# Op_Amp_Sig_Process.net
KiCad netlist of a schematic drawn in Altium Designer
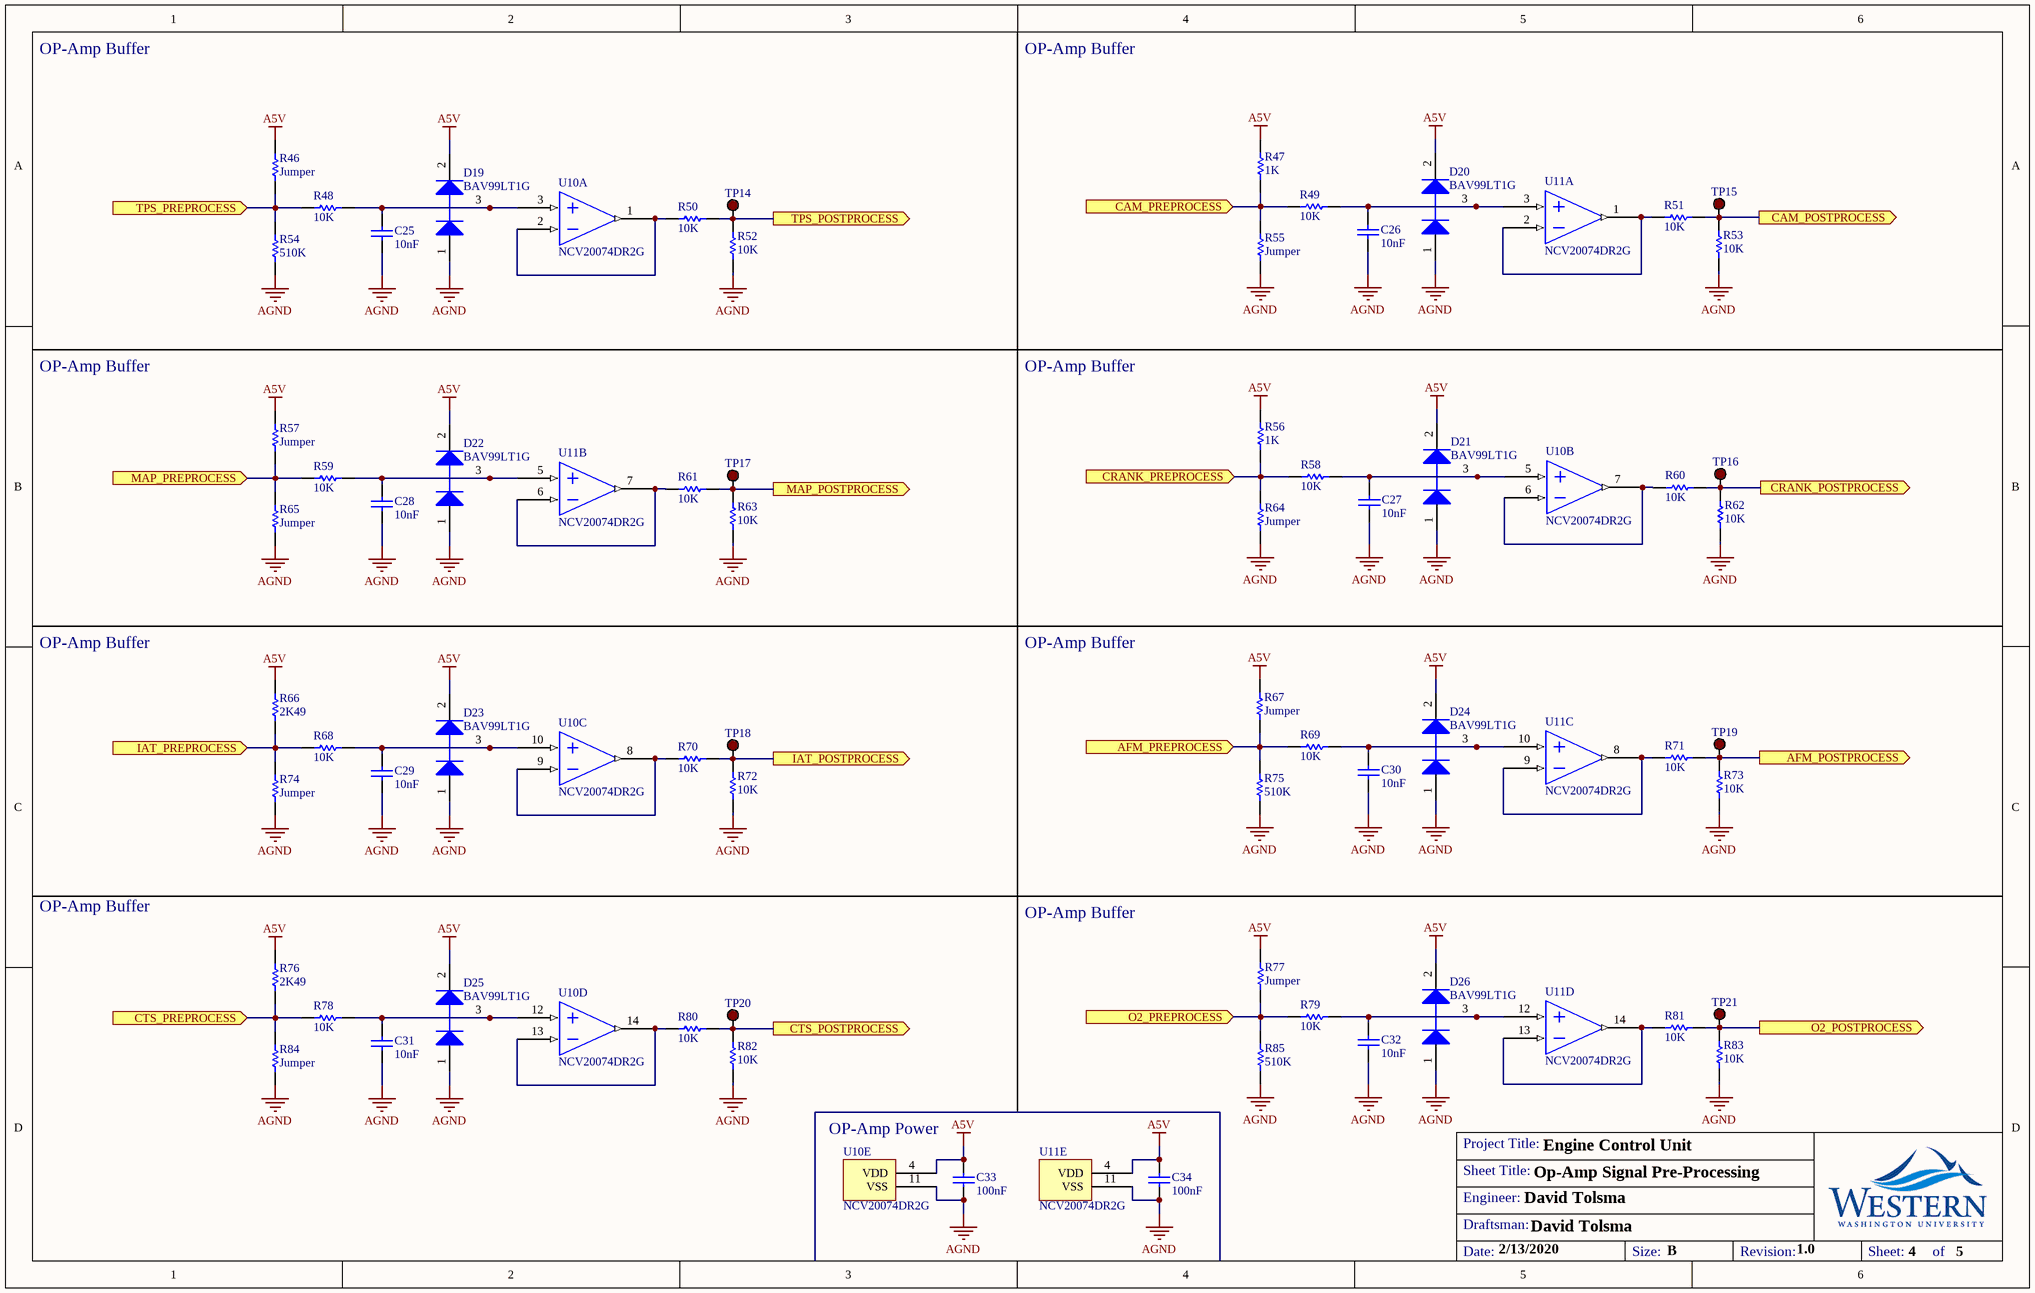
[diagram p0: Op_Amp_Sig_Process.SchDoc]

(export (version "E")
  (design (tool "Eeschema 10.0.6"))
  (components
    (comp (ref "C25")
      (value "10nF")
      (footprint "CAPC0603(1608)100_M")
      (description "CAP 10nF 50V ±5% 0603 (1608 Metric) Thickness 1mm SMD")
      (fields (field (name "TOLERANCE") "Â±5%"))
      (libsource (lib "Altium Content Vault") (part "CAP"))
    )
    (comp (ref "C26")
      (value "10nF")
      (footprint "CAPC0603(1608)100_M")
      (description "CAP 10nF 50V ±5% 0603 (1608 Metric) Thickness 1mm SMD")
      (fields (field (name "TOLERANCE") "Â±5%"))
      (libsource (lib "Altium Content Vault") (part "CAP"))
    )
    (comp (ref "C27")
      (value "10nF")
      (footprint "CAPC0603(1608)100_M")
      (description "CAP 10nF 50V ±5% 0603 (1608 Metric) Thickness 1mm SMD")
      (fields (field (name "TOLERANCE") "Â±5%"))
      (libsource (lib "Altium Content Vault") (part "CAP"))
    )
    (comp (ref "C28")
      (value "10nF")
      (footprint "CAPC0603(1608)100_M")
      (description "CAP 10nF 50V ±5% 0603 (1608 Metric) Thickness 1mm SMD")
      (fields (field (name "TOLERANCE") "Â±5%"))
      (libsource (lib "Altium Content Vault") (part "CAP"))
    )
    (comp (ref "C29")
      (value "10nF")
      (footprint "CAPC0603(1608)100_M")
      (description "CAP 10nF 50V ±5% 0603 (1608 Metric) Thickness 1mm SMD")
      (fields (field (name "TOLERANCE") "Â±5%"))
      (libsource (lib "Altium Content Vault") (part "CAP"))
    )
    (comp (ref "C30")
      (value "10nF")
      (footprint "CAPC0603(1608)100_M")
      (description "CAP 10nF 50V ±5% 0603 (1608 Metric) Thickness 1mm SMD")
      (fields (field (name "TOLERANCE") "Â±5%"))
      (libsource (lib "Altium Content Vault") (part "CAP"))
    )
    (comp (ref "C31")
      (value "10nF")
      (footprint "CAPC0603(1608)100_M")
      (description "CAP 10nF 50V ±5% 0603 (1608 Metric) Thickness 1mm SMD")
      (fields (field (name "TOLERANCE") "Â±5%"))
      (libsource (lib "Altium Content Vault") (part "CAP"))
    )
    (comp (ref "C32")
      (value "10nF")
      (footprint "CAPC0603(1608)100_M")
      (description "CAP 10nF 50V ±5% 0603 (1608 Metric) Thickness 1mm SMD")
      (fields (field (name "TOLERANCE") "Â±5%"))
      (libsource (lib "Altium Content Vault") (part "CAP"))
    )
    (comp (ref "C33")
      (value "100nF")
      (footprint "CAPC0603(1608)100_M")
      (description "CAP 100nF 10V ±10% 0603 (1608 Metric) Thickness 1mm SMD")
      (fields (field (name "TOLERANCE") "Â±10%"))
      (libsource (lib "Altium Content Vault") (part "CAP"))
    )
    (comp (ref "C34")
      (value "100nF")
      (footprint "CAPC0603(1608)100_M")
      (description "CAP 100nF 10V ±10% 0603 (1608 Metric) Thickness 1mm SMD")
      (fields (field (name "TOLERANCE") "Â±10%"))
      (libsource (lib "Altium Content Vault") (part "CAP"))
    )
    (comp (ref "D19")
      (value "BAV99LT1G")
      (footprint "ONSC-SOT-23-3-318-08_V")
      (description "Dual Series Switching Diodes, 3-Pin SOT-23, Pb-Free, Tape and Reel")
      (fields (field (name "MANUFACTURER") "On Semiconductor"))
      (libsource (lib "Altium Content Vault") (part "ONSC-D-A1K2C3-3"))
    )
    (comp (ref "D20")
      (value "BAV99LT1G")
      (footprint "ONSC-SOT-23-3-318-08_V")
      (description "Dual Series Switching Diodes, 3-Pin SOT-23, Pb-Free, Tape and Reel")
      (fields (field (name "MANUFACTURER") "On Semiconductor"))
      (libsource (lib "Altium Content Vault") (part "ONSC-D-A1K2C3-3"))
    )
    (comp (ref "D21")
      (value "BAV99LT1G")
      (footprint "ONSC-SOT-23-3-318-08_V")
      (description "Dual Series Switching Diodes, 3-Pin SOT-23, Pb-Free, Tape and Reel")
      (fields (field (name "MANUFACTURER") "On Semiconductor"))
      (libsource (lib "Altium Content Vault") (part "ONSC-D-A1K2C3-3"))
    )
    (comp (ref "D22")
      (value "BAV99LT1G")
      (footprint "ONSC-SOT-23-3-318-08_V")
      (description "Dual Series Switching Diodes, 3-Pin SOT-23, Pb-Free, Tape and Reel")
      (fields (field (name "MANUFACTURER") "On Semiconductor"))
      (libsource (lib "Altium Content Vault") (part "ONSC-D-A1K2C3-3"))
    )
    (comp (ref "D23")
      (value "BAV99LT1G")
      (footprint "ONSC-SOT-23-3-318-08_V")
      (description "Dual Series Switching Diodes, 3-Pin SOT-23, Pb-Free, Tape and Reel")
      (fields (field (name "MANUFACTURER") "On Semiconductor"))
      (libsource (lib "Altium Content Vault") (part "ONSC-D-A1K2C3-3"))
    )
    (comp (ref "D24")
      (value "BAV99LT1G")
      (footprint "ONSC-SOT-23-3-318-08_V")
      (description "Dual Series Switching Diodes, 3-Pin SOT-23, Pb-Free, Tape and Reel")
      (fields (field (name "MANUFACTURER") "On Semiconductor"))
      (libsource (lib "Altium Content Vault") (part "ONSC-D-A1K2C3-3"))
    )
    (comp (ref "D25")
      (value "BAV99LT1G")
      (footprint "ONSC-SOT-23-3-318-08_V")
      (description "Dual Series Switching Diodes, 3-Pin SOT-23, Pb-Free, Tape and Reel")
      (fields (field (name "MANUFACTURER") "On Semiconductor"))
      (libsource (lib "Altium Content Vault") (part "ONSC-D-A1K2C3-3"))
    )
    (comp (ref "D26")
      (value "BAV99LT1G")
      (footprint "ONSC-SOT-23-3-318-08_V")
      (description "Dual Series Switching Diodes, 3-Pin SOT-23, Pb-Free, Tape and Reel")
      (fields (field (name "MANUFACTURER") "On Semiconductor"))
      (libsource (lib "Altium Content Vault") (part "ONSC-D-A1K2C3-3"))
    )
    (comp (ref "R46")
      (value "Jumper")
      (footprint "RESC0603(1608)_M")
      (description "Jumper 0603 (1608 Metric)")
      (fields (field (name "POWER") "None"))
      (libsource (lib "Altium Content Vault") (part "RES"))
    )
    (comp (ref "R47")
      (value "1K")
      (footprint "RESC0603(1608)_M")
      (description "1K 0.1W 1% 0603 (1608 Metric)  SMD")
      (fields (field (name "TOLERANCE") "1 %") (field (name "POWER") "0.1 W"))
      (libsource (lib "Altium Content Vault") (part "RES"))
    )
    (comp (ref "R48")
      (value "10K")
      (footprint "RESC0603(1608)_M")
      (description "10K 0.1W 1% 0603 (1608 Metric)  SMD")
      (fields (field (name "POWER") "0.1 W") (field (name "TOLERANCE") "1 %"))
      (libsource (lib "Altium Content Vault") (part "RES"))
    )
    (comp (ref "R49")
      (value "10K")
      (footprint "RESC0603(1608)_M")
      (description "10K 0.1W 1% 0603 (1608 Metric)  SMD")
      (fields (field (name "POWER") "0.1 W") (field (name "TOLERANCE") "1 %"))
      (libsource (lib "Altium Content Vault") (part "RES"))
    )
    (comp (ref "R50")
      (value "10K")
      (footprint "RESC0603(1608)_M")
      (description "10K 0.1W 1% 0603 (1608 Metric)  SMD")
      (fields (field (name "POWER") "0.1 W") (field (name "TOLERANCE") "1 %"))
      (libsource (lib "Altium Content Vault") (part "RES"))
    )
    (comp (ref "R51")
      (value "10K")
      (footprint "RESC0603(1608)_M")
      (description "10K 0.1W 1% 0603 (1608 Metric)  SMD")
      (fields (field (name "POWER") "0.1 W") (field (name "TOLERANCE") "1 %"))
      (libsource (lib "Altium Content Vault") (part "RES"))
    )
    (comp (ref "R52")
      (value "10K")
      (footprint "RESC0603(1608)_M")
      (description "10K 0.1W 1% 0603 (1608 Metric)  SMD")
      (fields (field (name "POWER") "0.1 W") (field (name "TOLERANCE") "1 %"))
      (libsource (lib "Altium Content Vault") (part "RES"))
    )
    (comp (ref "R53")
      (value "10K")
      (footprint "RESC0603(1608)_M")
      (description "10K 0.1W 1% 0603 (1608 Metric)  SMD")
      (fields (field (name "POWER") "0.1 W") (field (name "TOLERANCE") "1 %"))
      (libsource (lib "Altium Content Vault") (part "RES"))
    )
    (comp (ref "R54")
      (value "510K")
      (footprint "RESC0603(1608)_M")
      (description "510K 0.1W 1% 0603 (1608 Metric)  SMD")
      (fields (field (name "TOLERANCE") "1 %") (field (name "POWER") "0.1 W"))
      (libsource (lib "Altium Content Vault") (part "RES"))
    )
    (comp (ref "R55")
      (value "Jumper")
      (footprint "RESC0603(1608)_M")
      (description "Jumper 0603 (1608 Metric)")
      (fields (field (name "POWER") "None"))
      (libsource (lib "Altium Content Vault") (part "RES"))
    )
    (comp (ref "R56")
      (value "1K")
      (footprint "RESC0603(1608)_M")
      (description "1K 0.1W 1% 0603 (1608 Metric)  SMD")
      (fields (field (name "TOLERANCE") "1 %") (field (name "POWER") "0.1 W"))
      (libsource (lib "Altium Content Vault") (part "RES"))
    )
    (comp (ref "R57")
      (value "Jumper")
      (footprint "RESC0603(1608)_M")
      (description "Jumper 0603 (1608 Metric)")
      (fields (field (name "POWER") "None"))
      (libsource (lib "Altium Content Vault") (part "RES"))
    )
    (comp (ref "R58")
      (value "10K")
      (footprint "RESC0603(1608)_M")
      (description "10K 0.1W 1% 0603 (1608 Metric)  SMD")
      (fields (field (name "POWER") "0.1 W") (field (name "TOLERANCE") "1 %"))
      (libsource (lib "Altium Content Vault") (part "RES"))
    )
    (comp (ref "R59")
      (value "10K")
      (footprint "RESC0603(1608)_M")
      (description "10K 0.1W 1% 0603 (1608 Metric)  SMD")
      (fields (field (name "POWER") "0.1 W") (field (name "TOLERANCE") "1 %"))
      (libsource (lib "Altium Content Vault") (part "RES"))
    )
    (comp (ref "R60")
      (value "10K")
      (footprint "RESC0603(1608)_M")
      (description "10K 0.1W 1% 0603 (1608 Metric)  SMD")
      (fields (field (name "POWER") "0.1 W") (field (name "TOLERANCE") "1 %"))
      (libsource (lib "Altium Content Vault") (part "RES"))
    )
    (comp (ref "R61")
      (value "10K")
      (footprint "RESC0603(1608)_M")
      (description "10K 0.1W 1% 0603 (1608 Metric)  SMD")
      (fields (field (name "POWER") "0.1 W") (field (name "TOLERANCE") "1 %"))
      (libsource (lib "Altium Content Vault") (part "RES"))
    )
    (comp (ref "R62")
      (value "10K")
      (footprint "RESC0603(1608)_M")
      (description "10K 0.1W 1% 0603 (1608 Metric)  SMD")
      (fields (field (name "POWER") "0.1 W") (field (name "TOLERANCE") "1 %"))
      (libsource (lib "Altium Content Vault") (part "RES"))
    )
    (comp (ref "R63")
      (value "10K")
      (footprint "RESC0603(1608)_M")
      (description "10K 0.1W 1% 0603 (1608 Metric)  SMD")
      (fields (field (name "POWER") "0.1 W") (field (name "TOLERANCE") "1 %"))
      (libsource (lib "Altium Content Vault") (part "RES"))
    )
    (comp (ref "R64")
      (value "Jumper")
      (footprint "RESC0603(1608)_M")
      (description "Jumper 0603 (1608 Metric)")
      (fields (field (name "POWER") "None"))
      (libsource (lib "Altium Content Vault") (part "RES"))
    )
    (comp (ref "R65")
      (value "Jumper")
      (footprint "RESC0603(1608)_M")
      (description "Jumper 0603 (1608 Metric)")
      (fields (field (name "POWER") "None"))
      (libsource (lib "Altium Content Vault") (part "RES"))
    )
    (comp (ref "R66")
      (value "2K49")
      (footprint "RESC0603(1608)_M")
      (description "2K49 0.1W 1% 0603 (1608 Metric)  SMD")
      (fields (field (name "TOLERANCE") "1 %") (field (name "POWER") "0.1 W"))
      (libsource (lib "Altium Content Vault") (part "RES"))
    )
    (comp (ref "R67")
      (value "Jumper")
      (footprint "RESC0603(1608)_M")
      (description "Jumper 0603 (1608 Metric)")
      (fields (field (name "POWER") "None"))
      (libsource (lib "Altium Content Vault") (part "RES"))
    )
    (comp (ref "R68")
      (value "10K")
      (footprint "RESC0603(1608)_M")
      (description "10K 0.1W 1% 0603 (1608 Metric)  SMD")
      (fields (field (name "POWER") "0.1 W") (field (name "TOLERANCE") "1 %"))
      (libsource (lib "Altium Content Vault") (part "RES"))
    )
    (comp (ref "R69")
      (value "10K")
      (footprint "RESC0603(1608)_M")
      (description "10K 0.1W 1% 0603 (1608 Metric)  SMD")
      (fields (field (name "POWER") "0.1 W") (field (name "TOLERANCE") "1 %"))
      (libsource (lib "Altium Content Vault") (part "RES"))
    )
    (comp (ref "R70")
      (value "10K")
      (footprint "RESC0603(1608)_M")
      (description "10K 0.1W 1% 0603 (1608 Metric)  SMD")
      (fields (field (name "POWER") "0.1 W") (field (name "TOLERANCE") "1 %"))
      (libsource (lib "Altium Content Vault") (part "RES"))
    )
    (comp (ref "R71")
      (value "10K")
      (footprint "RESC0603(1608)_M")
      (description "10K 0.1W 1% 0603 (1608 Metric)  SMD")
      (fields (field (name "POWER") "0.1 W") (field (name "TOLERANCE") "1 %"))
      (libsource (lib "Altium Content Vault") (part "RES"))
    )
    (comp (ref "R72")
      (value "10K")
      (footprint "RESC0603(1608)_M")
      (description "10K 0.1W 1% 0603 (1608 Metric)  SMD")
      (fields (field (name "POWER") "0.1 W") (field (name "TOLERANCE") "1 %"))
      (libsource (lib "Altium Content Vault") (part "RES"))
    )
    (comp (ref "R73")
      (value "10K")
      (footprint "RESC0603(1608)_M")
      (description "10K 0.1W 1% 0603 (1608 Metric)  SMD")
      (fields (field (name "POWER") "0.1 W") (field (name "TOLERANCE") "1 %"))
      (libsource (lib "Altium Content Vault") (part "RES"))
    )
    (comp (ref "R74")
      (value "Jumper")
      (footprint "RESC0603(1608)_M")
      (description "Jumper 0603 (1608 Metric)")
      (fields (field (name "POWER") "None"))
      (libsource (lib "Altium Content Vault") (part "RES"))
    )
    (comp (ref "R75")
      (value "510K")
      (footprint "RESC0603(1608)_M")
      (description "510K 0.1W 1% 0603 (1608 Metric)  SMD")
      (fields (field (name "TOLERANCE") "1 %") (field (name "POWER") "0.1 W"))
      (libsource (lib "Altium Content Vault") (part "RES"))
    )
    (comp (ref "R76")
      (value "2K49")
      (footprint "RESC0603(1608)_M")
      (description "2K49 0.1W 1% 0603 (1608 Metric)  SMD")
      (fields (field (name "TOLERANCE") "1 %") (field (name "POWER") "0.1 W"))
      (libsource (lib "Altium Content Vault") (part "RES"))
    )
    (comp (ref "R77")
      (value "Jumper")
      (footprint "RESC0603(1608)_M")
      (description "Jumper 0603 (1608 Metric)")
      (fields (field (name "POWER") "None"))
      (libsource (lib "Altium Content Vault") (part "RES"))
    )
    (comp (ref "R78")
      (value "10K")
      (footprint "RESC0603(1608)_M")
      (description "10K 0.1W 1% 0603 (1608 Metric)  SMD")
      (fields (field (name "POWER") "0.1 W") (field (name "TOLERANCE") "1 %"))
      (libsource (lib "Altium Content Vault") (part "RES"))
    )
    (comp (ref "R79")
      (value "10K")
      (footprint "RESC0603(1608)_M")
      (description "10K 0.1W 1% 0603 (1608 Metric)  SMD")
      (fields (field (name "POWER") "0.1 W") (field (name "TOLERANCE") "1 %"))
      (libsource (lib "Altium Content Vault") (part "RES"))
    )
    (comp (ref "R80")
      (value "10K")
      (footprint "RESC0603(1608)_M")
      (description "10K 0.1W 1% 0603 (1608 Metric)  SMD")
      (fields (field (name "POWER") "0.1 W") (field (name "TOLERANCE") "1 %"))
      (libsource (lib "Altium Content Vault") (part "RES"))
    )
    (comp (ref "R81")
      (value "10K")
      (footprint "RESC0603(1608)_M")
      (description "10K 0.1W 1% 0603 (1608 Metric)  SMD")
      (fields (field (name "POWER") "0.1 W") (field (name "TOLERANCE") "1 %"))
      (libsource (lib "Altium Content Vault") (part "RES"))
    )
    (comp (ref "R82")
      (value "10K")
      (footprint "RESC0603(1608)_M")
      (description "10K 0.1W 1% 0603 (1608 Metric)  SMD")
      (fields (field (name "POWER") "0.1 W") (field (name "TOLERANCE") "1 %"))
      (libsource (lib "Altium Content Vault") (part "RES"))
    )
    (comp (ref "R83")
      (value "10K")
      (footprint "RESC0603(1608)_M")
      (description "10K 0.1W 1% 0603 (1608 Metric)  SMD")
      (fields (field (name "POWER") "0.1 W") (field (name "TOLERANCE") "1 %"))
      (libsource (lib "Altium Content Vault") (part "RES"))
    )
    (comp (ref "R84")
      (value "Jumper")
      (footprint "RESC0603(1608)_M")
      (description "Jumper 0603 (1608 Metric)")
      (fields (field (name "POWER") "None"))
      (libsource (lib "Altium Content Vault") (part "RES"))
    )
    (comp (ref "R85")
      (value "510K")
      (footprint "RESC0603(1608)_M")
      (description "510K 0.1W 1% 0603 (1608 Metric)  SMD")
      (fields (field (name "TOLERANCE") "1 %") (field (name "POWER") "0.1 W"))
      (libsource (lib "Altium Content Vault") (part "RES"))
    )
    (comp (ref "TP14")
      (value "5001")
      (footprint "Keystone_5001")
      (description "TEST POINT PC MINI .040\"D BLACK")
      (fields (field (name "MANUFACTURER") "Keystone Electronics"))
      (libsource (lib "WWUEE_SchematicLibrary") (part "TEST POINT"))
    )
    (comp (ref "TP15")
      (value "5001")
      (footprint "Keystone_5001")
      (description "TEST POINT PC MINI .040\"D BLACK")
      (fields (field (name "MANUFACTURER") "Keystone Electronics"))
      (libsource (lib "WWUEE_SchematicLibrary") (part "TEST POINT"))
    )
    (comp (ref "TP16")
      (value "5001")
      (footprint "Keystone_5001")
      (description "TEST POINT PC MINI .040\"D BLACK")
      (fields (field (name "MANUFACTURER") "Keystone Electronics"))
      (libsource (lib "WWUEE_SchematicLibrary") (part "TEST POINT"))
    )
    (comp (ref "TP17")
      (value "5001")
      (footprint "Keystone_5001")
      (description "TEST POINT PC MINI .040\"D BLACK")
      (fields (field (name "MANUFACTURER") "Keystone Electronics"))
      (libsource (lib "WWUEE_SchematicLibrary") (part "TEST POINT"))
    )
    (comp (ref "TP18")
      (value "5001")
      (footprint "Keystone_5001")
      (description "TEST POINT PC MINI .040\"D BLACK")
      (fields (field (name "MANUFACTURER") "Keystone Electronics"))
      (libsource (lib "WWUEE_SchematicLibrary") (part "TEST POINT"))
    )
    (comp (ref "TP19")
      (value "5001")
      (footprint "Keystone_5001")
      (description "TEST POINT PC MINI .040\"D BLACK")
      (fields (field (name "MANUFACTURER") "Keystone Electronics"))
      (libsource (lib "WWUEE_SchematicLibrary") (part "TEST POINT"))
    )
    (comp (ref "TP20")
      (value "5001")
      (footprint "Keystone_5001")
      (description "TEST POINT PC MINI .040\"D BLACK")
      (fields (field (name "MANUFACTURER") "Keystone Electronics"))
      (libsource (lib "WWUEE_SchematicLibrary") (part "TEST POINT"))
    )
    (comp (ref "TP21")
      (value "5001")
      (footprint "Keystone_5001")
      (description "TEST POINT PC MINI .040\"D BLACK")
      (fields (field (name "MANUFACTURER") "Keystone Electronics"))
      (libsource (lib "WWUEE_SchematicLibrary") (part "TEST POINT"))
    )
    (comp (ref "U10")
      (value "NCV20074DR2G")
      (footprint "NCV20074DR2G")
      (libsource (lib "ECU") (part "NCV20074DR2G"))
    )
    (comp (ref "U11")
      (value "NCV20074DR2G")
      (footprint "NCV20074DR2G")
      (libsource (lib "ECU") (part "NCV20074DR2G"))
    )
  )
  (nets
    (net (code "1") (name "/AFM_POSTPROCESS") (class "Default")
      (node (ref "R71") (pin "2") (pinfunction "2_2") (pintype "passive"))
      (node (ref "R73") (pin "2") (pinfunction "2_2") (pintype "passive"))
      (node (ref "TP19") (pin "1") (pinfunction "TP_1") (pintype "passive"))
    )
    (net (code "2") (name "/AFM_PREPROCESS") (class "Default")
      (node (ref "R67") (pin "1") (pinfunction "1_1") (pintype "passive"))
      (node (ref "R69") (pin "1") (pinfunction "1_1") (pintype "passive"))
      (node (ref "R75") (pin "2") (pinfunction "2_2") (pintype "passive"))
    )
    (net (code "3") (name "/CAM_POSTPROCESS") (class "Default")
      (node (ref "R51") (pin "2") (pinfunction "2_2") (pintype "passive"))
      (node (ref "R53") (pin "2") (pinfunction "2_2") (pintype "passive"))
      (node (ref "TP15") (pin "1") (pinfunction "TP_1") (pintype "passive"))
    )
    (net (code "4") (name "/CAM_PREPROCESS") (class "Default")
      (node (ref "R47") (pin "1") (pinfunction "1_1") (pintype "passive"))
      (node (ref "R49") (pin "1") (pinfunction "1_1") (pintype "passive"))
      (node (ref "R55") (pin "2") (pinfunction "2_2") (pintype "passive"))
    )
    (net (code "5") (name "/CRANK_POSTPROCESS") (class "Default")
      (node (ref "R60") (pin "2") (pinfunction "2_2") (pintype "passive"))
      (node (ref "R62") (pin "2") (pinfunction "2_2") (pintype "passive"))
      (node (ref "TP16") (pin "1") (pinfunction "TP_1") (pintype "passive"))
    )
    (net (code "6") (name "/CRANK_PREPROCESS") (class "Default")
      (node (ref "R56") (pin "1") (pinfunction "1_1") (pintype "passive"))
      (node (ref "R58") (pin "1") (pinfunction "1_1") (pintype "passive"))
      (node (ref "R64") (pin "2") (pinfunction "2_2") (pintype "passive"))
    )
    (net (code "7") (name "/CTS_POSTPROCESS") (class "Default")
      (node (ref "R80") (pin "2") (pinfunction "2_2") (pintype "passive"))
      (node (ref "R82") (pin "2") (pinfunction "2_2") (pintype "passive"))
      (node (ref "TP20") (pin "1") (pinfunction "TP_1") (pintype "passive"))
    )
    (net (code "8") (name "/CTS_PREPROCESS") (class "Default")
      (node (ref "R76") (pin "1") (pinfunction "1_1") (pintype "passive"))
      (node (ref "R78") (pin "1") (pinfunction "1_1") (pintype "passive"))
      (node (ref "R84") (pin "2") (pinfunction "2_2") (pintype "passive"))
    )
    (net (code "9") (name "/IAT_POSTPROCESS") (class "Default")
      (node (ref "R70") (pin "2") (pinfunction "2_2") (pintype "passive"))
      (node (ref "R72") (pin "2") (pinfunction "2_2") (pintype "passive"))
      (node (ref "TP18") (pin "1") (pinfunction "TP_1") (pintype "passive"))
    )
    (net (code "10") (name "/IAT_PREPROCESS") (class "Default")
      (node (ref "R66") (pin "1") (pinfunction "1_1") (pintype "passive"))
      (node (ref "R68") (pin "1") (pinfunction "1_1") (pintype "passive"))
      (node (ref "R74") (pin "2") (pinfunction "2_2") (pintype "passive"))
    )
    (net (code "11") (name "/MAP_POSTPROCESS") (class "Default")
      (node (ref "R61") (pin "2") (pinfunction "2_2") (pintype "passive"))
      (node (ref "R63") (pin "2") (pinfunction "2_2") (pintype "passive"))
      (node (ref "TP17") (pin "1") (pinfunction "TP_1") (pintype "passive"))
    )
    (net (code "12") (name "/MAP_PREPROCESS") (class "Default")
      (node (ref "R57") (pin "1") (pinfunction "1_1") (pintype "passive"))
      (node (ref "R59") (pin "1") (pinfunction "1_1") (pintype "passive"))
      (node (ref "R65") (pin "2") (pinfunction "2_2") (pintype "passive"))
    )
    (net (code "13") (name "/O2_POSTPROCESS") (class "Default")
      (node (ref "R81") (pin "2") (pinfunction "2_2") (pintype "passive"))
      (node (ref "R83") (pin "2") (pinfunction "2_2") (pintype "passive"))
      (node (ref "TP21") (pin "1") (pinfunction "TP_1") (pintype "passive"))
    )
    (net (code "14") (name "/O2_PREPROCESS") (class "Default")
      (node (ref "R77") (pin "1") (pinfunction "1_1") (pintype "passive"))
      (node (ref "R79") (pin "1") (pinfunction "1_1") (pintype "passive"))
      (node (ref "R85") (pin "2") (pinfunction "2_2") (pintype "passive"))
    )
    (net (code "15") (name "/TPS_POSTPROCESS") (class "Default")
      (node (ref "R50") (pin "2") (pinfunction "2_2") (pintype "passive"))
      (node (ref "R52") (pin "2") (pinfunction "2_2") (pintype "passive"))
      (node (ref "TP14") (pin "1") (pinfunction "TP_1") (pintype "passive"))
    )
    (net (code "16") (name "/TPS_PREPROCESS") (class "Default")
      (node (ref "R46") (pin "1") (pinfunction "1_1") (pintype "passive"))
      (node (ref "R48") (pin "1") (pinfunction "1_1") (pintype "passive"))
      (node (ref "R54") (pin "2") (pinfunction "2_2") (pintype "passive"))
    )
    (net (code "17") (name "A5V") (class "Default")
      (node (ref "C33") (pin "2") (pinfunction "2_2") (pintype "passive"))
      (node (ref "C34") (pin "2") (pinfunction "2_2") (pintype "passive"))
      (node (ref "D19") (pin "2") (pinfunction "K_2") (pintype "passive"))
      (node (ref "D20") (pin "2") (pinfunction "K_2") (pintype "passive"))
      (node (ref "D21") (pin "2") (pinfunction "K_2") (pintype "passive"))
      (node (ref "D22") (pin "2") (pinfunction "K_2") (pintype "passive"))
      (node (ref "D23") (pin "2") (pinfunction "K_2") (pintype "passive"))
      (node (ref "D24") (pin "2") (pinfunction "K_2") (pintype "passive"))
      (node (ref "D25") (pin "2") (pinfunction "K_2") (pintype "passive"))
      (node (ref "D26") (pin "2") (pinfunction "K_2") (pintype "passive"))
      (node (ref "R46") (pin "2") (pinfunction "2_2") (pintype "passive"))
      (node (ref "R47") (pin "2") (pinfunction "2_2") (pintype "passive"))
      (node (ref "R56") (pin "2") (pinfunction "2_2") (pintype "passive"))
      (node (ref "R57") (pin "2") (pinfunction "2_2") (pintype "passive"))
      (node (ref "R66") (pin "2") (pinfunction "2_2") (pintype "passive"))
      (node (ref "R67") (pin "2") (pinfunction "2_2") (pintype "passive"))
      (node (ref "R76") (pin "2") (pinfunction "2_2") (pintype "passive"))
      (node (ref "R77") (pin "2") (pinfunction "2_2") (pintype "passive"))
      (node (ref "U10") (pin "4") (pinfunction "VDD_4") (pintype "power_in"))
      (node (ref "U11") (pin "4") (pinfunction "VDD_4") (pintype "power_in"))
    )
    (net (code "18") (name "AGND") (class "Default")
      (node (ref "C25") (pin "1") (pinfunction "1_1") (pintype "passive"))
      (node (ref "C26") (pin "1") (pinfunction "1_1") (pintype "passive"))
      (node (ref "C27") (pin "1") (pinfunction "1_1") (pintype "passive"))
      (node (ref "C28") (pin "1") (pinfunction "1_1") (pintype "passive"))
      (node (ref "C29") (pin "1") (pinfunction "1_1") (pintype "passive"))
      (node (ref "C30") (pin "1") (pinfunction "1_1") (pintype "passive"))
      (node (ref "C31") (pin "1") (pinfunction "1_1") (pintype "passive"))
      (node (ref "C32") (pin "1") (pinfunction "1_1") (pintype "passive"))
      (node (ref "C33") (pin "1") (pinfunction "1_1") (pintype "passive"))
      (node (ref "C34") (pin "1") (pinfunction "1_1") (pintype "passive"))
      (node (ref "D19") (pin "1") (pinfunction "A_1") (pintype "passive"))
      (node (ref "D20") (pin "1") (pinfunction "A_1") (pintype "passive"))
      (node (ref "D21") (pin "1") (pinfunction "A_1") (pintype "passive"))
      (node (ref "D22") (pin "1") (pinfunction "A_1") (pintype "passive"))
      (node (ref "D23") (pin "1") (pinfunction "A_1") (pintype "passive"))
      (node (ref "D24") (pin "1") (pinfunction "A_1") (pintype "passive"))
      (node (ref "D25") (pin "1") (pinfunction "A_1") (pintype "passive"))
      (node (ref "D26") (pin "1") (pinfunction "A_1") (pintype "passive"))
      (node (ref "R52") (pin "1") (pinfunction "1_1") (pintype "passive"))
      (node (ref "R53") (pin "1") (pinfunction "1_1") (pintype "passive"))
      (node (ref "R54") (pin "1") (pinfunction "1_1") (pintype "passive"))
      (node (ref "R55") (pin "1") (pinfunction "1_1") (pintype "passive"))
      (node (ref "R62") (pin "1") (pinfunction "1_1") (pintype "passive"))
      (node (ref "R63") (pin "1") (pinfunction "1_1") (pintype "passive"))
      (node (ref "R64") (pin "1") (pinfunction "1_1") (pintype "passive"))
      (node (ref "R65") (pin "1") (pinfunction "1_1") (pintype "passive"))
      (node (ref "R72") (pin "1") (pinfunction "1_1") (pintype "passive"))
      (node (ref "R73") (pin "1") (pinfunction "1_1") (pintype "passive"))
      (node (ref "R74") (pin "1") (pinfunction "1_1") (pintype "passive"))
      (node (ref "R75") (pin "1") (pinfunction "1_1") (pintype "passive"))
      (node (ref "R82") (pin "1") (pinfunction "1_1") (pintype "passive"))
      (node (ref "R83") (pin "1") (pinfunction "1_1") (pintype "passive"))
      (node (ref "R84") (pin "1") (pinfunction "1_1") (pintype "passive"))
      (node (ref "R85") (pin "1") (pinfunction "1_1") (pintype "passive"))
      (node (ref "U10") (pin "11") (pinfunction "VSS_11") (pintype "power_in"))
      (node (ref "U11") (pin "11") (pinfunction "VSS_11") (pintype "power_in"))
    )
    (net (code "19") (name "Net-(D19-K{slash}A)") (class "Default")
      (node (ref "C25") (pin "2") (pinfunction "2_2") (pintype "passive"))
      (node (ref "D19") (pin "3") (pinfunction "K/A_3") (pintype "passive"))
      (node (ref "R48") (pin "2") (pinfunction "2_2") (pintype "passive"))
      (node (ref "U10") (pin "3") (pinfunction "IN1+_3") (pintype "input"))
    )
    (net (code "20") (name "Net-(D20-K{slash}A)") (class "Default")
      (node (ref "C26") (pin "2") (pinfunction "2_2") (pintype "passive"))
      (node (ref "D20") (pin "3") (pinfunction "K/A_3") (pintype "passive"))
      (node (ref "R49") (pin "2") (pinfunction "2_2") (pintype "passive"))
      (node (ref "U11") (pin "3") (pinfunction "IN1+_3") (pintype "input"))
    )
    (net (code "21") (name "Net-(D21-K{slash}A)") (class "Default")
      (node (ref "C27") (pin "2") (pinfunction "2_2") (pintype "passive"))
      (node (ref "D21") (pin "3") (pinfunction "K/A_3") (pintype "passive"))
      (node (ref "R58") (pin "2") (pinfunction "2_2") (pintype "passive"))
      (node (ref "U10") (pin "5") (pinfunction "IN2+_5") (pintype "input"))
    )
    (net (code "22") (name "Net-(D22-K{slash}A)") (class "Default")
      (node (ref "C28") (pin "2") (pinfunction "2_2") (pintype "passive"))
      (node (ref "D22") (pin "3") (pinfunction "K/A_3") (pintype "passive"))
      (node (ref "R59") (pin "2") (pinfunction "2_2") (pintype "passive"))
      (node (ref "U11") (pin "5") (pinfunction "IN2+_5") (pintype "input"))
    )
    (net (code "23") (name "Net-(D23-K{slash}A)") (class "Default")
      (node (ref "C29") (pin "2") (pinfunction "2_2") (pintype "passive"))
      (node (ref "D23") (pin "3") (pinfunction "K/A_3") (pintype "passive"))
      (node (ref "R68") (pin "2") (pinfunction "2_2") (pintype "passive"))
      (node (ref "U10") (pin "10") (pinfunction "IN3+_10") (pintype "input"))
    )
    (net (code "24") (name "Net-(D24-K{slash}A)") (class "Default")
      (node (ref "C30") (pin "2") (pinfunction "2_2") (pintype "passive"))
      (node (ref "D24") (pin "3") (pinfunction "K/A_3") (pintype "passive"))
      (node (ref "R69") (pin "2") (pinfunction "2_2") (pintype "passive"))
      (node (ref "U11") (pin "10") (pinfunction "IN3+_10") (pintype "input"))
    )
    (net (code "25") (name "Net-(D25-K{slash}A)") (class "Default")
      (node (ref "C31") (pin "2") (pinfunction "2_2") (pintype "passive"))
      (node (ref "D25") (pin "3") (pinfunction "K/A_3") (pintype "passive"))
      (node (ref "R78") (pin "2") (pinfunction "2_2") (pintype "passive"))
      (node (ref "U10") (pin "12") (pinfunction "IN4+_12") (pintype "input"))
    )
    (net (code "26") (name "Net-(D26-K{slash}A)") (class "Default")
      (node (ref "C32") (pin "2") (pinfunction "2_2") (pintype "passive"))
      (node (ref "D26") (pin "3") (pinfunction "K/A_3") (pintype "passive"))
      (node (ref "R79") (pin "2") (pinfunction "2_2") (pintype "passive"))
      (node (ref "U11") (pin "12") (pinfunction "IN4+_12") (pintype "input"))
    )
    (net (code "27") (name "Net-(U10A-IN1-)") (class "Default")
      (node (ref "R50") (pin "1") (pinfunction "1_1") (pintype "passive"))
      (node (ref "U10") (pin "1") (pinfunction "OUT1_1") (pintype "output"))
      (node (ref "U10") (pin "2") (pinfunction "IN1-_2") (pintype "input"))
    )
    (net (code "28") (name "Net-(U10B-IN2-)") (class "Default")
      (node (ref "R60") (pin "1") (pinfunction "1_1") (pintype "passive"))
      (node (ref "U10") (pin "6") (pinfunction "IN2-_6") (pintype "input"))
      (node (ref "U10") (pin "7") (pinfunction "OUT2_7") (pintype "output"))
    )
    (net (code "29") (name "Net-(U10C-IN3-)") (class "Default")
      (node (ref "R70") (pin "1") (pinfunction "1_1") (pintype "passive"))
      (node (ref "U10") (pin "8") (pinfunction "OUT3_8") (pintype "output"))
      (node (ref "U10") (pin "9") (pinfunction "IN3-_9") (pintype "input"))
    )
    (net (code "30") (name "Net-(U10D-IN4-)") (class "Default")
      (node (ref "R80") (pin "1") (pinfunction "1_1") (pintype "passive"))
      (node (ref "U10") (pin "13") (pinfunction "IN4-_13") (pintype "input"))
      (node (ref "U10") (pin "14") (pinfunction "OUT4_14") (pintype "output"))
    )
    (net (code "31") (name "Net-(U11A-IN1-)") (class "Default")
      (node (ref "R51") (pin "1") (pinfunction "1_1") (pintype "passive"))
      (node (ref "U11") (pin "1") (pinfunction "OUT1_1") (pintype "output"))
      (node (ref "U11") (pin "2") (pinfunction "IN1-_2") (pintype "input"))
    )
    (net (code "32") (name "Net-(U11B-IN2-)") (class "Default")
      (node (ref "R61") (pin "1") (pinfunction "1_1") (pintype "passive"))
      (node (ref "U11") (pin "6") (pinfunction "IN2-_6") (pintype "input"))
      (node (ref "U11") (pin "7") (pinfunction "OUT2_7") (pintype "output"))
    )
    (net (code "33") (name "Net-(U11C-IN3-)") (class "Default")
      (node (ref "R71") (pin "1") (pinfunction "1_1") (pintype "passive"))
      (node (ref "U11") (pin "8") (pinfunction "OUT3_8") (pintype "output"))
      (node (ref "U11") (pin "9") (pinfunction "IN3-_9") (pintype "input"))
    )
    (net (code "34") (name "Net-(U11D-IN4-)") (class "Default")
      (node (ref "R81") (pin "1") (pinfunction "1_1") (pintype "passive"))
      (node (ref "U11") (pin "13") (pinfunction "IN4-_13") (pintype "input"))
      (node (ref "U11") (pin "14") (pinfunction "OUT4_14") (pintype "output"))
    )
  )
)
